# growinov0.net
KiCad netlist of a schematic drawn in EAGLE
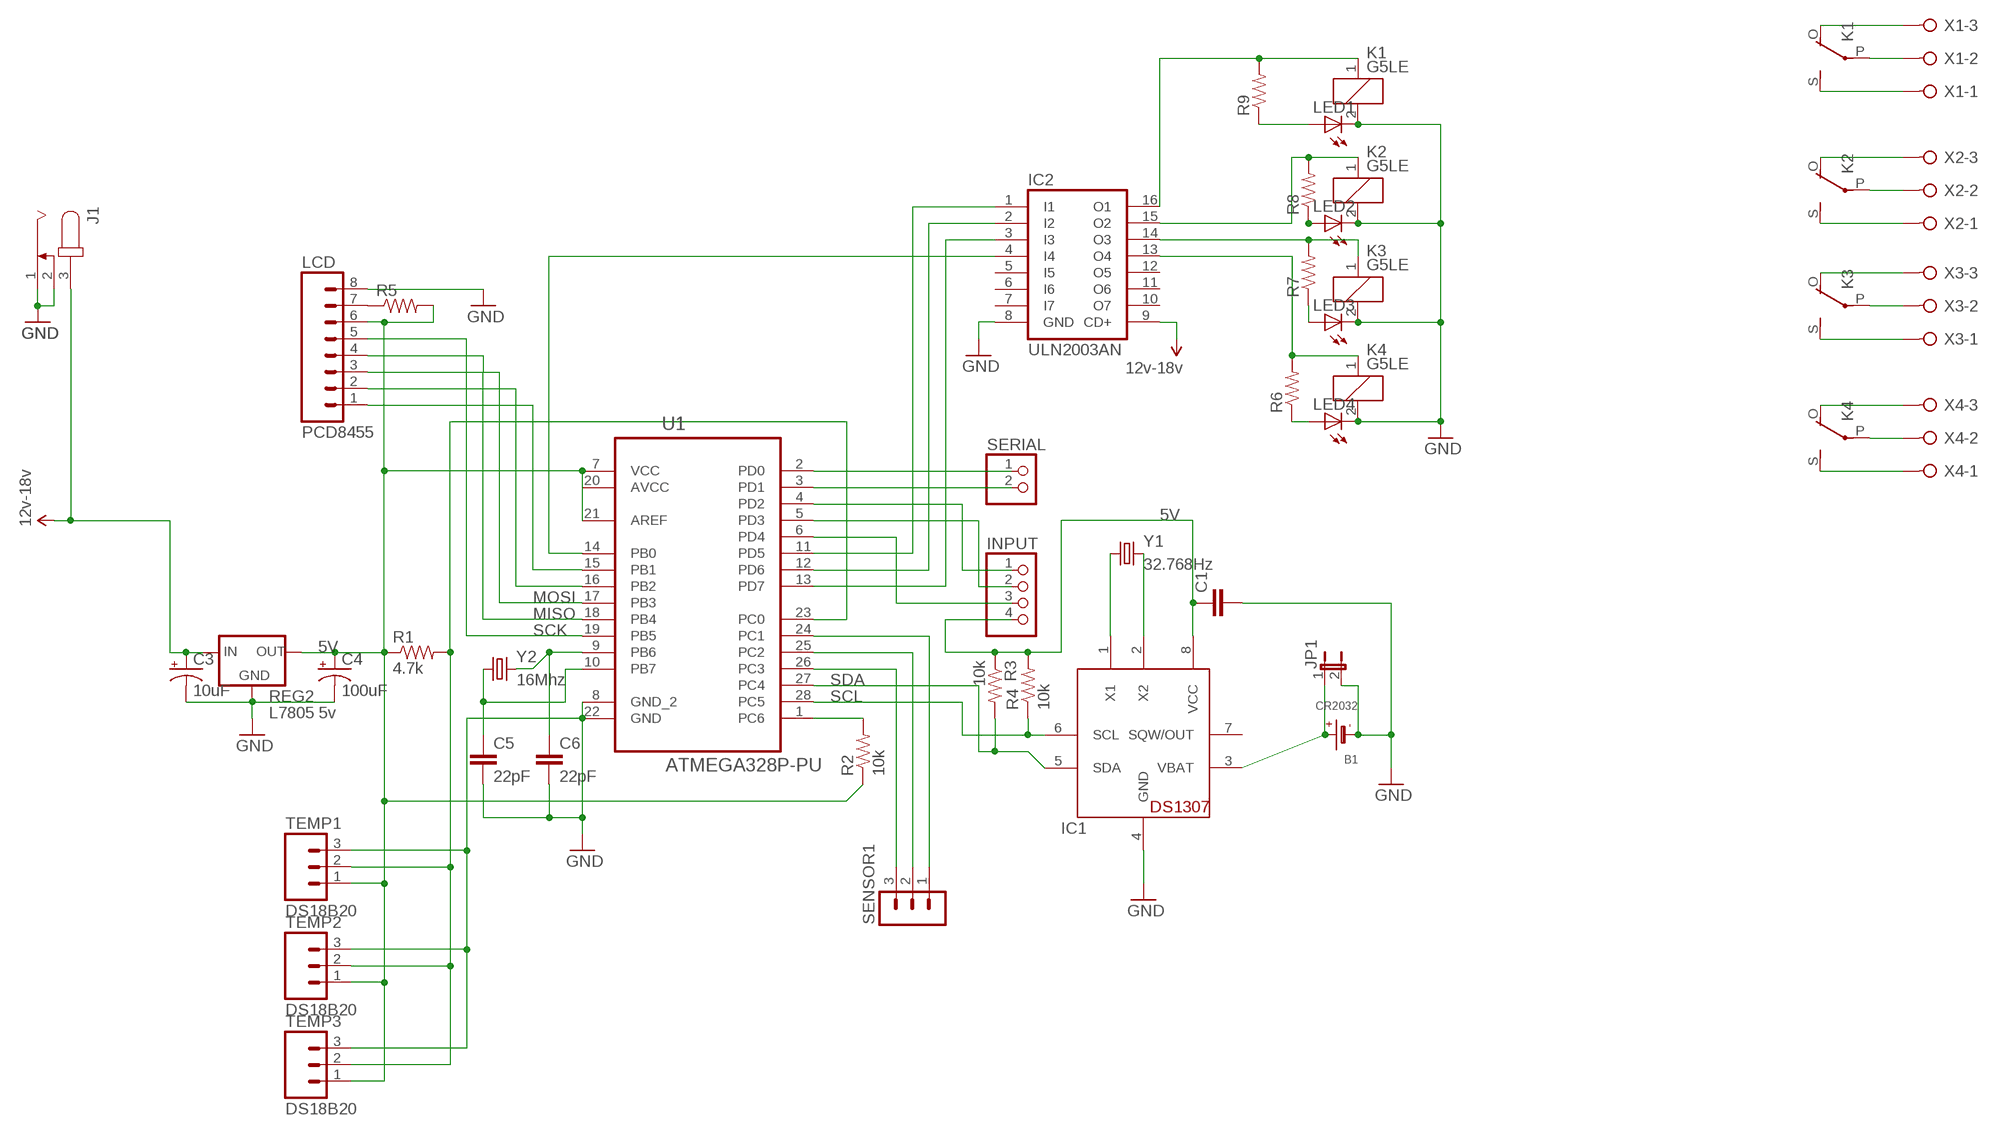
[diagram p0: schematic, sheet 1]

(export (version "E")
  (design (tool "Eeschema 10.0.6"))
  (components
    (comp (ref "B1")
      (value "CR2032")
      (footprint "eagle-import:CR2032")
      (libsource (lib "eagle-import") (part "BATTERYCR2032"))
    )
    (comp (ref "C1")
      (value "CAPPTH1")
      (footprint "eagle-import:CAP-PTH-5MM")
      (libsource (lib "eagle-import") (part "CAPPTH1"))
    )
    (comp (ref "C3")
      (value "10uF")
      (footprint "eagle-import:CPOL-RADIAL-10UF-25V")
      (libsource (lib "eagle-import") (part "CAP_POLPTH2"))
    )
    (comp (ref "C4")
      (value "100uF")
      (footprint "eagle-import:CPOL-RADIAL-100UF-25V")
      (libsource (lib "eagle-import") (part "CAP_POLPTH1"))
    )
    (comp (ref "C5")
      (value "22pF")
      (footprint "eagle-import:CAP-PTH-SMALL-KIT")
      (libsource (lib "eagle-import") (part "SparkFun-Passives_CAPKIT"))
    )
    (comp (ref "C6")
      (value "22pF")
      (footprint "eagle-import:CAP-PTH-SMALL-KIT")
      (libsource (lib "eagle-import") (part "SparkFun-Passives_CAPKIT"))
    )
    (comp (ref "IC1")
      (value "DS1307")
      (footprint "eagle-import:DIL08")
      (libsource (lib "eagle-import") (part "DS1307"))
    )
    (comp (ref "IC2")
      (value "ULN2003AN")
      (footprint "eagle-import:DIL16")
      (libsource (lib "eagle-import") (part "ULN2003AN"))
    )
    (comp (ref "INPUT")
      (value "PINHD-1X4")
      (footprint "eagle-import:1X04")
      (libsource (lib "eagle-import") (part "PINHD-1X4"))
    )
    (comp (ref "J1")
      (value "JACK-PLUG0")
      (footprint "eagle-import:SPC4077")
      (libsource (lib "eagle-import") (part "JACK-PLUG0"))
    )
    (comp (ref "JP1")
      (value "JUMPER-2PTH")
      (footprint "eagle-import:1X02")
      (libsource (lib "eagle-import") (part "JUMPER-2PTH"))
    )
    (comp (ref "K1")
      (value "G5LE")
      (footprint "eagle-import:G5LE")
      (libsource (lib "eagle-import") (part "G5LE"))
    )
    (comp (ref "K2")
      (value "G5LE")
      (footprint "eagle-import:G5LE")
      (libsource (lib "eagle-import") (part "G5LE"))
    )
    (comp (ref "K3")
      (value "G5LE")
      (footprint "eagle-import:G5LE")
      (libsource (lib "eagle-import") (part "G5LE"))
    )
    (comp (ref "K4")
      (value "G5LE")
      (footprint "eagle-import:G5LE")
      (libsource (lib "eagle-import") (part "G5LE"))
    )
    (comp (ref "LCD")
      (value "PCD8455")
      (footprint "eagle-import:1X08")
      (libsource (lib "eagle-import") (part "M081X08"))
    )
    (comp (ref "LED1")
      (value "LED3MM")
      (footprint "eagle-import:LED3MM")
      (libsource (lib "eagle-import") (part "LED3MM"))
    )
    (comp (ref "LED2")
      (value "LED3MM")
      (footprint "eagle-import:LED3MM")
      (libsource (lib "eagle-import") (part "LED3MM"))
    )
    (comp (ref "LED3")
      (value "LED3MM")
      (footprint "eagle-import:LED3MM")
      (libsource (lib "eagle-import") (part "LED3MM"))
    )
    (comp (ref "LED4")
      (value "LED3MM")
      (footprint "eagle-import:LED3MM")
      (libsource (lib "eagle-import") (part "LED3MM"))
    )
    (comp (ref "R1")
      (value "4.7k")
      (footprint "eagle-import:AXIAL-0.4")
      (libsource (lib "eagle-import") (part "RESISTORPTH-1/4W"))
    )
    (comp (ref "R2")
      (value "10k")
      (footprint "eagle-import:AXIAL-0.4")
      (libsource (lib "eagle-import") (part "SparkFun-Resistors_RESISTORPTH-1/4W"))
    )
    (comp (ref "R3")
      (value "10k")
      (footprint "eagle-import:AXIAL-0.4")
      (libsource (lib "eagle-import") (part "RESISTORPTH-1/4W"))
    )
    (comp (ref "R4")
      (value "10k")
      (footprint "eagle-import:AXIAL-0.4")
      (libsource (lib "eagle-import") (part "RESISTORPTH-1/4W"))
    )
    (comp (ref "R5")
      (value "RESISTORPTH-1/4W-VERT")
      (footprint "eagle-import:AXIAL-0.1")
      (libsource (lib "eagle-import") (part "RESISTORPTH-1/4W-VERT"))
    )
    (comp (ref "R6")
      (value "RESISTORPTH-1/4W-VERT")
      (footprint "eagle-import:AXIAL-0.1")
      (libsource (lib "eagle-import") (part "RESISTORPTH-1/4W-VERT"))
    )
    (comp (ref "R7")
      (value "RESISTORPTH-1/4W-VERT")
      (footprint "eagle-import:AXIAL-0.1")
      (libsource (lib "eagle-import") (part "RESISTORPTH-1/4W-VERT"))
    )
    (comp (ref "R8")
      (value "RESISTORPTH-1/4W-VERT")
      (footprint "eagle-import:AXIAL-0.1")
      (libsource (lib "eagle-import") (part "RESISTORPTH-1/4W-VERT"))
    )
    (comp (ref "R9")
      (value "RESISTORPTH-1/4W-VERT")
      (footprint "eagle-import:AXIAL-0.1")
      (libsource (lib "eagle-import") (part "RESISTORPTH-1/4W-VERT"))
    )
    (comp (ref "REG2")
      (value "L7805 5v")
      (footprint "eagle-import:78XXL")
      (libsource (lib "eagle-import") (part "V_REG_78XXSIDE"))
    )
    (comp (ref "SENSOR1")
      (value "MA03-1")
      (footprint "eagle-import:MA03-1")
      (libsource (lib "eagle-import") (part "MA03-1"))
    )
    (comp (ref "SERIAL")
      (value "PINHD-1X2")
      (footprint "eagle-import:1X02")
      (libsource (lib "eagle-import") (part "PINHD-1X2"))
    )
    (comp (ref "TEMP1")
      (value "DS18B20")
      (footprint "eagle-import:MOLEX-1X3")
      (libsource (lib "eagle-import") (part "M03POLAR"))
    )
    (comp (ref "TEMP2")
      (value "DS18B20")
      (footprint "eagle-import:MOLEX-1X3")
      (libsource (lib "eagle-import") (part "M03POLAR"))
    )
    (comp (ref "TEMP3")
      (value "DS18B20")
      (footprint "eagle-import:MOLEX-1X3")
      (libsource (lib "eagle-import") (part "M03POLAR"))
    )
    (comp (ref "U1")
      (value "ATMEGA328P-PU")
      (footprint "eagle-import:DIP254P762X457-28")
      (libsource (lib "eagle-import") (part "ATMEGA328P-PU"))
    )
    (comp (ref "X1")
      (value "W237-3E")
      (footprint "eagle-import:W237-3E")
      (libsource (lib "eagle-import") (part "W237-3E"))
    )
    (comp (ref "X2")
      (value "W237-3E")
      (footprint "eagle-import:W237-3E")
      (libsource (lib "eagle-import") (part "W237-3E"))
    )
    (comp (ref "X3")
      (value "W237-3E")
      (footprint "eagle-import:W237-3E")
      (libsource (lib "eagle-import") (part "W237-3E"))
    )
    (comp (ref "X4")
      (value "W237-3E")
      (footprint "eagle-import:W237-3E")
      (libsource (lib "eagle-import") (part "W237-3E"))
    )
    (comp (ref "Y1")
      (value "32.768Hz")
      (footprint "eagle-import:TC26H")
      (libsource (lib "eagle-import") (part "CRYSTALTC26H"))
    )
    (comp (ref "Y2")
      (value "16Mhz")
      (footprint "eagle-import:HC49US")
      (libsource (lib "eagle-import") (part "CRYSTALHC49US"))
    )
  )
  (nets
    (net (code "1") (name "/5V") (class "Default")
      (node (ref "C1") (pin "1") (pinfunction "1_1") (pintype "passive"))
      (node (ref "C4") (pin "1") (pinfunction "+_1") (pintype "passive"))
      (node (ref "IC1") (pin "8") (pinfunction "VCC_8") (pintype "power_in"))
      (node (ref "INPUT") (pin "4") (pinfunction "4_4") (pintype "passive"))
      (node (ref "LCD") (pin "6") (pinfunction "6_6") (pintype "passive"))
      (node (ref "R1") (pin "P$1") (pinfunction "1_P$1") (pintype "passive"))
      (node (ref "R2") (pin "P$1") (pinfunction "1_P$1") (pintype "passive"))
      (node (ref "R3") (pin "P$1") (pinfunction "1_P$1") (pintype "passive"))
      (node (ref "R4") (pin "P$2") (pinfunction "2_P$2") (pintype "passive"))
      (node (ref "R5") (pin "P$2") (pinfunction "2_P$2") (pintype "passive"))
      (node (ref "REG2") (pin "OUT") (pinfunction "OUT_OUT") (pintype "output"))
      (node (ref "TEMP1") (pin "1") (pinfunction "1_1") (pintype "passive"))
      (node (ref "TEMP2") (pin "1") (pinfunction "1_1") (pintype "passive"))
      (node (ref "TEMP3") (pin "1") (pinfunction "1_1") (pintype "passive"))
      (node (ref "U1") (pin "20") (pinfunction "AVCC_20") (pintype "power_in"))
      (node (ref "U1") (pin "21") (pinfunction "AREF_21") (pintype "input"))
      (node (ref "U1") (pin "7") (pinfunction "VCC_7") (pintype "power_in"))
    )
    (net (code "2") (name "/MISO") (class "Default")
      (node (ref "LCD") (pin "4") (pinfunction "4_4") (pintype "passive"))
      (node (ref "U1") (pin "18") (pinfunction "PB4_18") (pintype "bidirectional"))
    )
    (net (code "3") (name "/MOSI") (class "Default")
      (node (ref "LCD") (pin "3") (pinfunction "3_3") (pintype "passive"))
      (node (ref "U1") (pin "17") (pinfunction "PB3_17") (pintype "bidirectional"))
    )
    (net (code "4") (name "/SCK") (class "Default")
      (node (ref "LCD") (pin "5") (pinfunction "5_5") (pintype "passive"))
      (node (ref "U1") (pin "19") (pinfunction "PB5_19") (pintype "bidirectional"))
    )
    (net (code "5") (name "/SCL") (class "Default")
      (node (ref "IC1") (pin "6") (pinfunction "SCL_6") (pintype "bidirectional"))
      (node (ref "R4") (pin "P$1") (pinfunction "1_P$1") (pintype "passive"))
      (node (ref "U1") (pin "28") (pinfunction "PC5_28") (pintype "bidirectional"))
    )
    (net (code "6") (name "/SDA") (class "Default")
      (node (ref "IC1") (pin "5") (pinfunction "SDA_5") (pintype "bidirectional"))
      (node (ref "R3") (pin "P$2") (pinfunction "2_P$2") (pintype "passive"))
      (node (ref "U1") (pin "27") (pinfunction "PC4_27") (pintype "bidirectional"))
    )
    (net (code "7") (name "12v-18v") (class "Default")
      (node (ref "C3") (pin "1") (pinfunction "+_1") (pintype "passive"))
      (node (ref "IC2") (pin "9") (pinfunction "CD+_9") (pintype "passive"))
      (node (ref "J1") (pin "3") (pinfunction "3_3") (pintype "passive"))
      (node (ref "REG2") (pin "IN") (pinfunction "IN_IN") (pintype "input"))
    )
    (net (code "8") (name "GND") (class "Default")
      (node (ref "B1") (pin "-") (pinfunction "-_-") (pintype "passive"))
      (node (ref "C1") (pin "2") (pinfunction "2_2") (pintype "passive"))
      (node (ref "C3") (pin "2") (pinfunction "-_2") (pintype "passive"))
      (node (ref "C4") (pin "2") (pinfunction "-_2") (pintype "passive"))
      (node (ref "C5") (pin "2") (pinfunction "2_2") (pintype "passive"))
      (node (ref "C6") (pin "2") (pinfunction "2_2") (pintype "passive"))
      (node (ref "IC1") (pin "4") (pinfunction "GND_4") (pintype "power_in"))
      (node (ref "IC2") (pin "8") (pinfunction "GND_8") (pintype "power_in"))
      (node (ref "J1") (pin "1") (pinfunction "1_1") (pintype "passive"))
      (node (ref "J1") (pin "2") (pinfunction "2_2") (pintype "passive"))
      (node (ref "JP1") (pin "2") (pinfunction "2_2") (pintype "passive"))
      (node (ref "K1") (pin "2") (pinfunction "2_2") (pintype "passive"))
      (node (ref "K2") (pin "2") (pinfunction "2_2") (pintype "passive"))
      (node (ref "K3") (pin "2") (pinfunction "2_2") (pintype "passive"))
      (node (ref "K4") (pin "2") (pinfunction "2_2") (pintype "passive"))
      (node (ref "LCD") (pin "8") (pinfunction "8_8") (pintype "passive"))
      (node (ref "LED1") (pin "K") (pinfunction "C_K") (pintype "passive"))
      (node (ref "LED2") (pin "K") (pinfunction "C_K") (pintype "passive"))
      (node (ref "LED3") (pin "K") (pinfunction "C_K") (pintype "passive"))
      (node (ref "LED4") (pin "K") (pinfunction "C_K") (pintype "passive"))
      (node (ref "REG2") (pin "GND") (pinfunction "GND_GND") (pintype "input"))
      (node (ref "TEMP1") (pin "3") (pinfunction "3_3") (pintype "passive"))
      (node (ref "TEMP2") (pin "3") (pinfunction "3_3") (pintype "passive"))
      (node (ref "TEMP3") (pin "3") (pinfunction "3_3") (pintype "passive"))
      (node (ref "U1") (pin "22") (pinfunction "GND_22") (pintype "passive"))
      (node (ref "U1") (pin "8") (pinfunction "GND_2_8") (pintype "passive"))
    )
    (net (code "9") (name "Net-(IC1-VBAT)") (class "Default")
      (node (ref "B1") (pin "+") (pinfunction "+_+") (pintype "passive"))
      (node (ref "IC1") (pin "3") (pinfunction "VBAT_3") (pintype "power_in"))
      (node (ref "JP1") (pin "1") (pinfunction "1_1") (pintype "passive"))
    )
    (net (code "10") (name "Net-(IC1-X1)") (class "Default")
      (node (ref "IC1") (pin "1") (pinfunction "X1_1") (pintype "passive"))
      (node (ref "Y1") (pin "1") (pinfunction "1_1") (pintype "passive"))
    )
    (net (code "11") (name "Net-(IC1-X2)") (class "Default")
      (node (ref "IC1") (pin "2") (pinfunction "X2_2") (pintype "passive"))
      (node (ref "Y1") (pin "2") (pinfunction "2_2") (pintype "passive"))
    )
    (net (code "12") (name "Net-(IC2-I1)") (class "Default")
      (node (ref "IC2") (pin "1") (pinfunction "I1_1") (pintype "input"))
      (node (ref "U1") (pin "11") (pinfunction "PD5_11") (pintype "bidirectional"))
    )
    (net (code "13") (name "Net-(IC2-I2)") (class "Default")
      (node (ref "IC2") (pin "2") (pinfunction "I2_2") (pintype "input"))
      (node (ref "U1") (pin "12") (pinfunction "PD6_12") (pintype "bidirectional"))
    )
    (net (code "14") (name "Net-(IC2-I3)") (class "Default")
      (node (ref "IC2") (pin "3") (pinfunction "I3_3") (pintype "input"))
      (node (ref "U1") (pin "13") (pinfunction "PD7_13") (pintype "bidirectional"))
    )
    (net (code "15") (name "Net-(IC2-I4)") (class "Default")
      (node (ref "IC2") (pin "4") (pinfunction "I4_4") (pintype "input"))
      (node (ref "U1") (pin "14") (pinfunction "PB0_14") (pintype "bidirectional"))
    )
    (net (code "16") (name "Net-(IC2-O1)") (class "Default")
      (node (ref "IC2") (pin "16") (pinfunction "O1_16") (pintype "open_collector"))
      (node (ref "K1") (pin "1") (pinfunction "1_1") (pintype "passive"))
      (node (ref "R9") (pin "P$2") (pinfunction "2_P$2") (pintype "passive"))
    )
    (net (code "17") (name "Net-(IC2-O2)") (class "Default")
      (node (ref "IC2") (pin "15") (pinfunction "O2_15") (pintype "open_collector"))
      (node (ref "K2") (pin "1") (pinfunction "1_1") (pintype "passive"))
      (node (ref "R8") (pin "P$2") (pinfunction "2_P$2") (pintype "passive"))
    )
    (net (code "18") (name "Net-(IC2-O3)") (class "Default")
      (node (ref "IC2") (pin "14") (pinfunction "O3_14") (pintype "open_collector"))
      (node (ref "K3") (pin "1") (pinfunction "1_1") (pintype "passive"))
      (node (ref "R7") (pin "P$2") (pinfunction "2_P$2") (pintype "passive"))
    )
    (net (code "19") (name "Net-(IC2-O4)") (class "Default")
      (node (ref "IC2") (pin "13") (pinfunction "O4_13") (pintype "open_collector"))
      (node (ref "K4") (pin "1") (pinfunction "1_1") (pintype "passive"))
      (node (ref "R6") (pin "P$2") (pinfunction "2_P$2") (pintype "passive"))
    )
    (net (code "20") (name "Net-(R1-2)") (class "Default")
      (node (ref "R1") (pin "P$2") (pinfunction "2_P$2") (pintype "passive"))
      (node (ref "TEMP1") (pin "2") (pinfunction "2_2") (pintype "passive"))
      (node (ref "TEMP2") (pin "2") (pinfunction "2_2") (pintype "passive"))
      (node (ref "TEMP3") (pin "2") (pinfunction "2_2") (pintype "passive"))
      (node (ref "U1") (pin "23") (pinfunction "PC0_23") (pintype "bidirectional"))
    )
    (net (code "21") (name "Net-(R2-2)") (class "Default")
      (node (ref "R2") (pin "P$2") (pinfunction "2_P$2") (pintype "passive"))
      (node (ref "U1") (pin "1") (pinfunction "PC6_1") (pintype "bidirectional"))
    )
    (net (code "22") (name "Net-(R5-1)") (class "Default")
      (node (ref "LCD") (pin "7") (pinfunction "7_7") (pintype "passive"))
      (node (ref "R5") (pin "P$1") (pinfunction "1_P$1") (pintype "passive"))
    )
    (net (code "23") (name "Net-(R6-1)") (class "Default")
      (node (ref "LED4") (pin "A") (pinfunction "A_A") (pintype "passive"))
      (node (ref "R6") (pin "P$1") (pinfunction "1_P$1") (pintype "passive"))
    )
    (net (code "24") (name "Net-(R7-1)") (class "Default")
      (node (ref "LED3") (pin "A") (pinfunction "A_A") (pintype "passive"))
      (node (ref "R7") (pin "P$1") (pinfunction "1_P$1") (pintype "passive"))
    )
    (net (code "25") (name "Net-(R8-1)") (class "Default")
      (node (ref "LED2") (pin "A") (pinfunction "A_A") (pintype "passive"))
      (node (ref "R8") (pin "P$1") (pinfunction "1_P$1") (pintype "passive"))
    )
    (net (code "26") (name "Net-(R9-1)") (class "Default")
      (node (ref "LED1") (pin "A") (pinfunction "A_A") (pintype "passive"))
      (node (ref "R9") (pin "P$1") (pinfunction "1_P$1") (pintype "passive"))
    )
    (net (code "27") (name "Net-(U1-PB1)") (class "Default")
      (node (ref "LCD") (pin "1") (pinfunction "1_1") (pintype "passive"))
      (node (ref "U1") (pin "15") (pinfunction "PB1_15") (pintype "bidirectional"))
    )
    (net (code "28") (name "Net-(U1-PB2)") (class "Default")
      (node (ref "LCD") (pin "2") (pinfunction "2_2") (pintype "passive"))
      (node (ref "U1") (pin "16") (pinfunction "PB2_16") (pintype "bidirectional"))
    )
    (net (code "29") (name "Net-(U1-PB6)") (class "Default")
      (node (ref "C6") (pin "1") (pinfunction "1_1") (pintype "passive"))
      (node (ref "U1") (pin "9") (pinfunction "PB6_9") (pintype "bidirectional"))
      (node (ref "Y2") (pin "2") (pinfunction "2_2") (pintype "passive"))
    )
    (net (code "30") (name "Net-(U1-PB7)") (class "Default")
      (node (ref "C5") (pin "1") (pinfunction "1_1") (pintype "passive"))
      (node (ref "U1") (pin "10") (pinfunction "PB7_10") (pintype "bidirectional"))
      (node (ref "Y2") (pin "1") (pinfunction "1_1") (pintype "passive"))
    )
    (net (code "31") (name "Net-(U1-PC1)") (class "Default")
      (node (ref "SENSOR1") (pin "1") (pinfunction "1_1") (pintype "passive"))
      (node (ref "U1") (pin "24") (pinfunction "PC1_24") (pintype "bidirectional"))
    )
    (net (code "32") (name "Net-(U1-PC2)") (class "Default")
      (node (ref "SENSOR1") (pin "2") (pinfunction "2_2") (pintype "passive"))
      (node (ref "U1") (pin "25") (pinfunction "PC2_25") (pintype "bidirectional"))
    )
    (net (code "33") (name "Net-(U1-PC3)") (class "Default")
      (node (ref "SENSOR1") (pin "3") (pinfunction "3_3") (pintype "passive"))
      (node (ref "U1") (pin "26") (pinfunction "PC3_26") (pintype "bidirectional"))
    )
    (net (code "34") (name "Net-(U1-PD0)") (class "Default")
      (node (ref "SERIAL") (pin "1") (pinfunction "1_1") (pintype "passive"))
      (node (ref "U1") (pin "2") (pinfunction "PD0_2") (pintype "bidirectional"))
    )
    (net (code "35") (name "Net-(U1-PD1)") (class "Default")
      (node (ref "SERIAL") (pin "2") (pinfunction "2_2") (pintype "passive"))
      (node (ref "U1") (pin "3") (pinfunction "PD1_3") (pintype "bidirectional"))
    )
    (net (code "36") (name "Net-(U1-PD2)") (class "Default")
      (node (ref "INPUT") (pin "1") (pinfunction "1_1") (pintype "passive"))
      (node (ref "U1") (pin "4") (pinfunction "PD2_4") (pintype "bidirectional"))
    )
    (net (code "37") (name "Net-(U1-PD3)") (class "Default")
      (node (ref "INPUT") (pin "2") (pinfunction "2_2") (pintype "passive"))
      (node (ref "U1") (pin "5") (pinfunction "PD3_5") (pintype "bidirectional"))
    )
    (net (code "38") (name "Net-(U1-PD4)") (class "Default")
      (node (ref "INPUT") (pin "3") (pinfunction "3_3") (pintype "passive"))
      (node (ref "U1") (pin "6") (pinfunction "PD4_6") (pintype "bidirectional"))
    )
    (net (code "39") (name "Net-(X1A-KL)") (class "Default")
      (node (ref "K1") (pin "S") (pinfunction "S_S") (pintype "passive"))
      (node (ref "X1") (pin "1") (pinfunction "KL_1") (pintype "passive"))
    )
    (net (code "40") (name "Net-(X1B-KL)") (class "Default")
      (node (ref "K1") (pin "P") (pinfunction "P_P") (pintype "passive"))
      (node (ref "X1") (pin "2") (pinfunction "KL_2") (pintype "passive"))
    )
    (net (code "41") (name "Net-(X1C-KL)") (class "Default")
      (node (ref "K1") (pin "O") (pinfunction "O_O") (pintype "passive"))
      (node (ref "X1") (pin "3") (pinfunction "KL_3") (pintype "passive"))
    )
    (net (code "42") (name "Net-(X2A-KL)") (class "Default")
      (node (ref "K2") (pin "S") (pinfunction "S_S") (pintype "passive"))
      (node (ref "X2") (pin "1") (pinfunction "KL_1") (pintype "passive"))
    )
    (net (code "43") (name "Net-(X2B-KL)") (class "Default")
      (node (ref "K2") (pin "P") (pinfunction "P_P") (pintype "passive"))
      (node (ref "X2") (pin "2") (pinfunction "KL_2") (pintype "passive"))
    )
    (net (code "44") (name "Net-(X2C-KL)") (class "Default")
      (node (ref "K2") (pin "O") (pinfunction "O_O") (pintype "passive"))
      (node (ref "X2") (pin "3") (pinfunction "KL_3") (pintype "passive"))
    )
    (net (code "45") (name "Net-(X3A-KL)") (class "Default")
      (node (ref "K3") (pin "S") (pinfunction "S_S") (pintype "passive"))
      (node (ref "X3") (pin "1") (pinfunction "KL_1") (pintype "passive"))
    )
    (net (code "46") (name "Net-(X3B-KL)") (class "Default")
      (node (ref "K3") (pin "P") (pinfunction "P_P") (pintype "passive"))
      (node (ref "X3") (pin "2") (pinfunction "KL_2") (pintype "passive"))
    )
    (net (code "47") (name "Net-(X3C-KL)") (class "Default")
      (node (ref "K3") (pin "O") (pinfunction "O_O") (pintype "passive"))
      (node (ref "X3") (pin "3") (pinfunction "KL_3") (pintype "passive"))
    )
    (net (code "48") (name "Net-(X4A-KL)") (class "Default")
      (node (ref "K4") (pin "S") (pinfunction "S_S") (pintype "passive"))
      (node (ref "X4") (pin "1") (pinfunction "KL_1") (pintype "passive"))
    )
    (net (code "49") (name "Net-(X4B-KL)") (class "Default")
      (node (ref "K4") (pin "P") (pinfunction "P_P") (pintype "passive"))
      (node (ref "X4") (pin "2") (pinfunction "KL_2") (pintype "passive"))
    )
    (net (code "50") (name "Net-(X4C-KL)") (class "Default")
      (node (ref "K4") (pin "O") (pinfunction "O_O") (pintype "passive"))
      (node (ref "X4") (pin "3") (pinfunction "KL_3") (pintype "passive"))
    )
    (net (code "51") (name "unconnected-(IC1-SQW{slash}OUT-Pad7)") (class "Default")
      (node (ref "IC1") (pin "7") (pinfunction "SQW/OUT_7") (pintype "bidirectional"))
    )
    (net (code "52") (name "unconnected-(IC2-I5-Pad5)") (class "Default")
      (node (ref "IC2") (pin "5") (pinfunction "I5_5") (pintype "input"))
    )
    (net (code "53") (name "unconnected-(IC2-I6-Pad6)") (class "Default")
      (node (ref "IC2") (pin "6") (pinfunction "I6_6") (pintype "input"))
    )
    (net (code "54") (name "unconnected-(IC2-I7-Pad7)") (class "Default")
      (node (ref "IC2") (pin "7") (pinfunction "I7_7") (pintype "input"))
    )
    (net (code "55") (name "unconnected-(IC2-O5-Pad12)") (class "Default")
      (node (ref "IC2") (pin "12") (pinfunction "O5_12") (pintype "open_collector"))
    )
    (net (code "56") (name "unconnected-(IC2-O6-Pad11)") (class "Default")
      (node (ref "IC2") (pin "11") (pinfunction "O6_11") (pintype "open_collector"))
    )
    (net (code "57") (name "unconnected-(IC2-O7-Pad10)") (class "Default")
      (node (ref "IC2") (pin "10") (pinfunction "O7_10") (pintype "open_collector"))
    )
  )
)
